# MidiIO.net
KiCad netlist of a schematic drawn in EAGLE
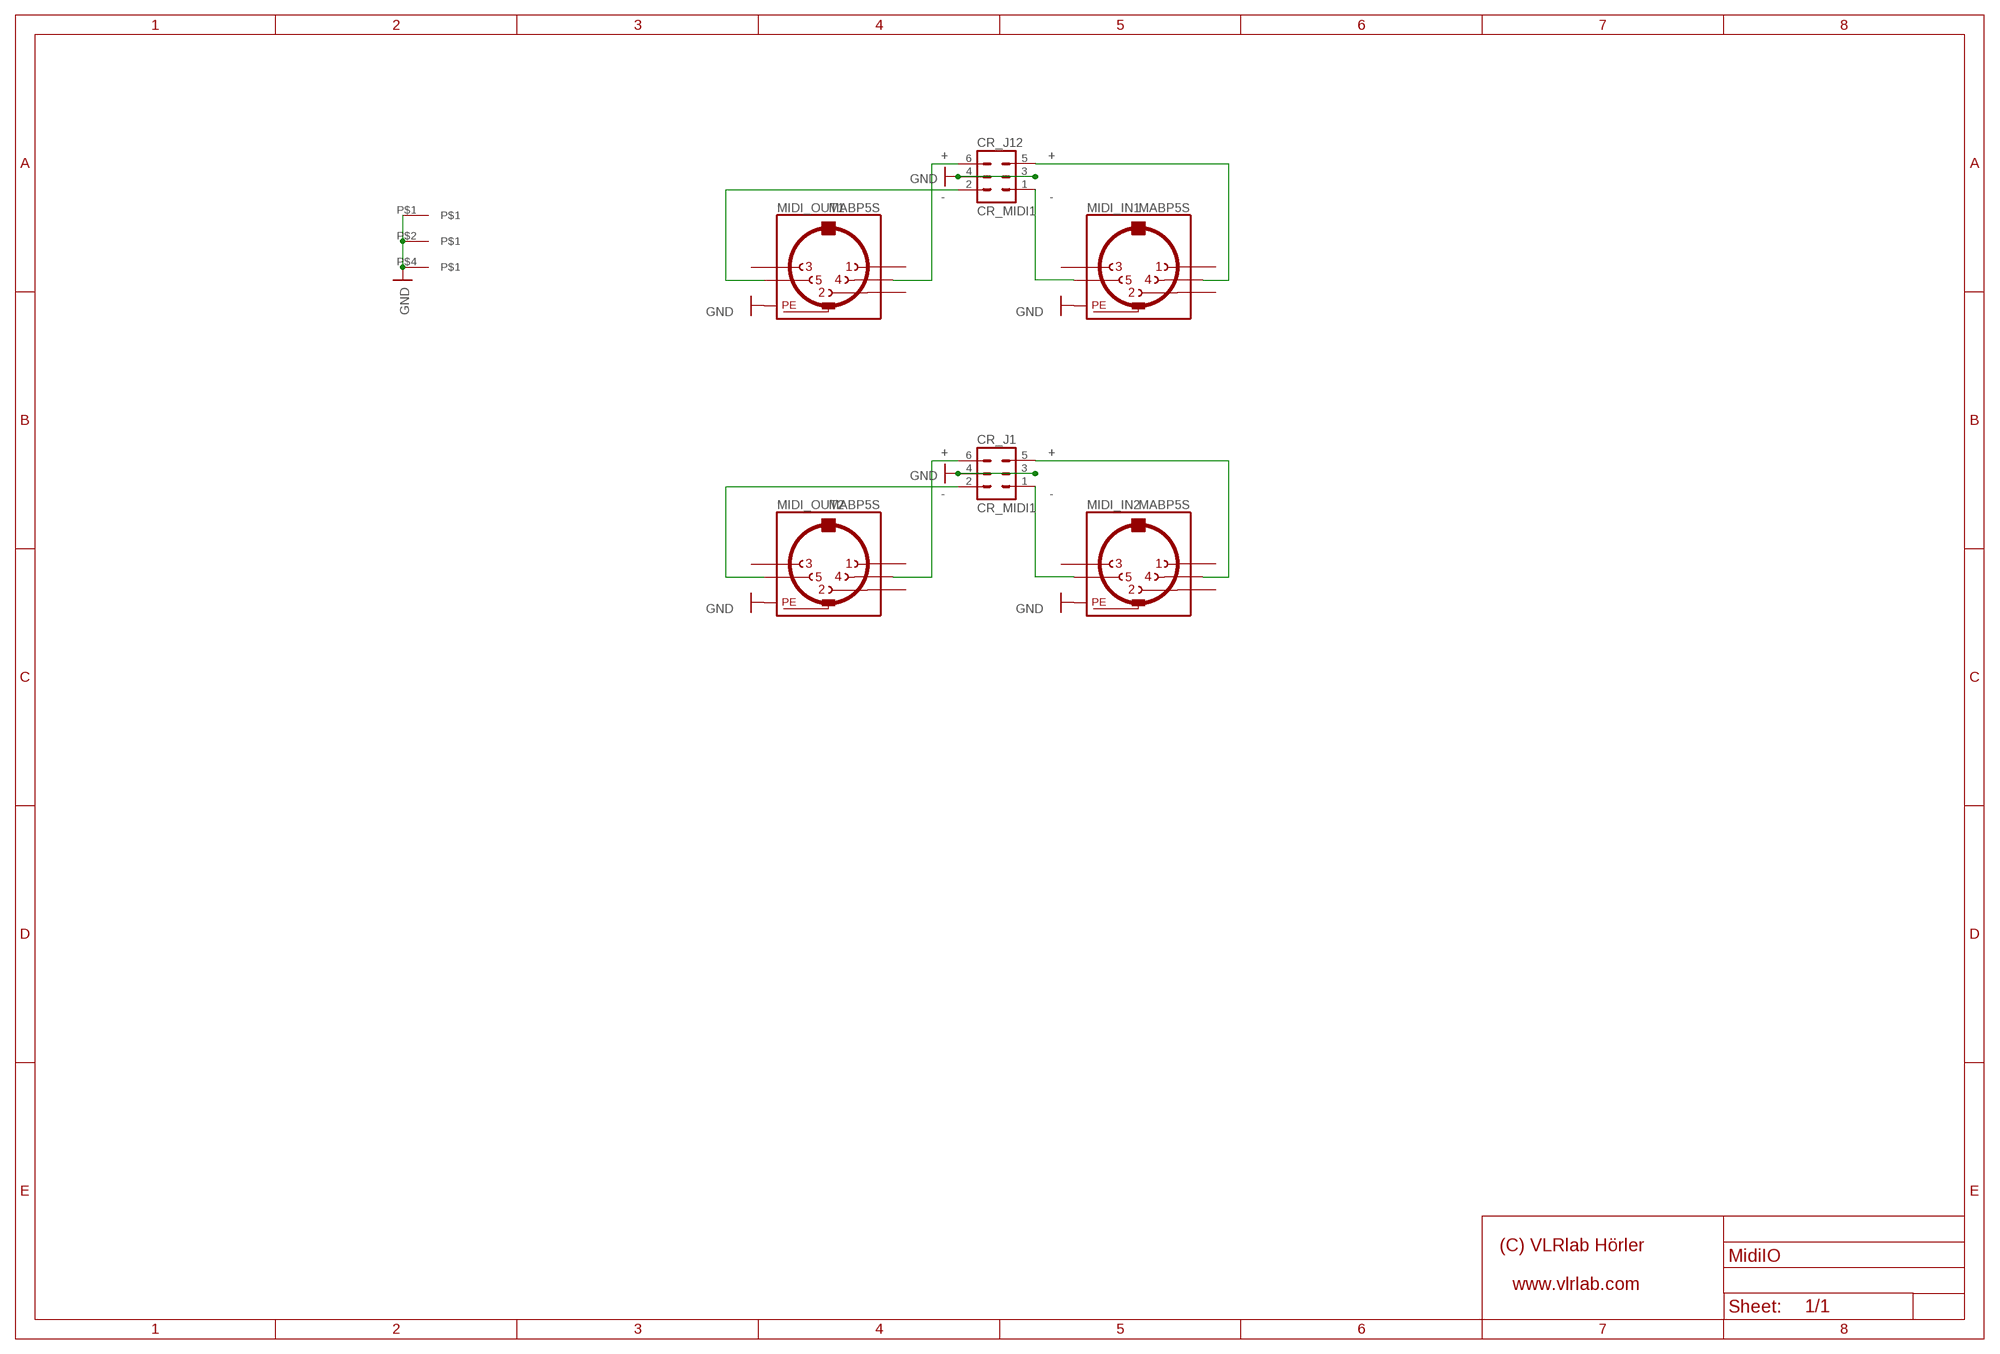
[diagram p0: schematic, sheet 1]

(export (version "E")
  (design (tool "Eeschema 10.0.6"))
  (components
    (comp (ref "CR_J1")
      (value "CR_MIDI1")
      (footprint "eagle-import:ML6")
      (libsource (lib "eagle-import") (part "ML6"))
    )
    (comp (ref "CR_J12")
      (value "CR_MIDI1")
      (footprint "eagle-import:ML6")
      (libsource (lib "eagle-import") (part "ML6"))
    )
    (comp (ref "MIDI_IN1")
      (value "MABP5S")
      (footprint "eagle-import:MABP5S")
      (libsource (lib "eagle-import") (part "MABP5S"))
    )
    (comp (ref "MIDI_IN2")
      (value "MABP5S")
      (footprint "eagle-import:MABP5S")
      (libsource (lib "eagle-import") (part "MABP5S"))
    )
    (comp (ref "MIDI_OUT1")
      (value "MABP5S")
      (footprint "eagle-import:MABP5S")
      (libsource (lib "eagle-import") (part "MABP5S"))
    )
    (comp (ref "MIDI_OUT2")
      (value "MABP5S")
      (footprint "eagle-import:MABP5S")
      (libsource (lib "eagle-import") (part "MABP5S"))
    )
    (comp (ref "U$2")
      (value "MIDIBOX_HALF_FRONTLINE")
      (footprint "eagle-import:MIDIBOX14X6-FRONTLINE")
      (libsource (lib "eagle-import") (part "MIDIBOX_HALF_FRONTLINE"))
    )
  )
  (nets
    (net (code "1") (name "GND") (class "Default")
      (node (ref "CR_J1") (pin "3") (pinfunction "3_3") (pintype "passive"))
      (node (ref "CR_J1") (pin "4") (pinfunction "4_4") (pintype "passive"))
      (node (ref "CR_J12") (pin "3") (pinfunction "3_3") (pintype "passive"))
      (node (ref "CR_J12") (pin "4") (pinfunction "4_4") (pintype "passive"))
      (node (ref "MIDI_IN1") (pin "PE") (pinfunction "PE_PE") (pintype "power_in"))
      (node (ref "MIDI_IN1") (pin "PE@") (pinfunction "PE_PE@") (pintype "power_in"))
      (node (ref "MIDI_IN2") (pin "PE") (pinfunction "PE_PE") (pintype "power_in"))
      (node (ref "MIDI_IN2") (pin "PE@") (pinfunction "PE_PE@") (pintype "power_in"))
      (node (ref "MIDI_OUT1") (pin "PE") (pinfunction "PE_PE") (pintype "power_in"))
      (node (ref "MIDI_OUT1") (pin "PE@") (pinfunction "PE_PE@") (pintype "power_in"))
      (node (ref "MIDI_OUT2") (pin "PE") (pinfunction "PE_PE") (pintype "power_in"))
      (node (ref "MIDI_OUT2") (pin "PE@") (pinfunction "PE_PE@") (pintype "power_in"))
      (node (ref "U$2") (pin "P$1") (pinfunction "P$1_P$1") (pintype "bidirectional"))
      (node (ref "U$2") (pin "P$2") (pinfunction "P$1_P$2") (pintype "bidirectional"))
      (node (ref "U$2") (pin "P$4") (pinfunction "P$1_P$4") (pintype "bidirectional"))
    )
    (net (code "2") (name "Net-(CR_J1-Pad1)") (class "Default")
      (node (ref "CR_J1") (pin "1") (pinfunction "1_1") (pintype "passive"))
      (node (ref "MIDI_IN2") (pin "5") (pinfunction "5_5") (pintype "passive"))
    )
    (net (code "3") (name "Net-(CR_J1-Pad2)") (class "Default")
      (node (ref "CR_J1") (pin "2") (pinfunction "2_2") (pintype "passive"))
      (node (ref "MIDI_OUT2") (pin "5") (pinfunction "5_5") (pintype "passive"))
    )
    (net (code "4") (name "Net-(CR_J1-Pad5)") (class "Default")
      (node (ref "CR_J1") (pin "5") (pinfunction "5_5") (pintype "passive"))
      (node (ref "MIDI_IN2") (pin "4") (pinfunction "4_4") (pintype "passive"))
    )
    (net (code "5") (name "Net-(CR_J1-Pad6)") (class "Default")
      (node (ref "CR_J1") (pin "6") (pinfunction "6_6") (pintype "passive"))
      (node (ref "MIDI_OUT2") (pin "4") (pinfunction "4_4") (pintype "passive"))
    )
    (net (code "6") (name "Net-(CR_J12-Pad1)") (class "Default")
      (node (ref "CR_J12") (pin "1") (pinfunction "1_1") (pintype "passive"))
      (node (ref "MIDI_IN1") (pin "5") (pinfunction "5_5") (pintype "passive"))
    )
    (net (code "7") (name "Net-(CR_J12-Pad2)") (class "Default")
      (node (ref "CR_J12") (pin "2") (pinfunction "2_2") (pintype "passive"))
      (node (ref "MIDI_OUT1") (pin "5") (pinfunction "5_5") (pintype "passive"))
    )
    (net (code "8") (name "Net-(CR_J12-Pad5)") (class "Default")
      (node (ref "CR_J12") (pin "5") (pinfunction "5_5") (pintype "passive"))
      (node (ref "MIDI_IN1") (pin "4") (pinfunction "4_4") (pintype "passive"))
    )
    (net (code "9") (name "Net-(CR_J12-Pad6)") (class "Default")
      (node (ref "CR_J12") (pin "6") (pinfunction "6_6") (pintype "passive"))
      (node (ref "MIDI_OUT1") (pin "4") (pinfunction "4_4") (pintype "passive"))
    )
    (net (code "10") (name "unconnected-(MIDI_IN1-Pad1)") (class "Default")
      (node (ref "MIDI_IN1") (pin "1") (pinfunction "1_1") (pintype "passive"))
    )
    (net (code "11") (name "unconnected-(MIDI_IN1-Pad2)") (class "Default")
      (node (ref "MIDI_IN1") (pin "2") (pinfunction "2_2") (pintype "passive"))
    )
    (net (code "12") (name "unconnected-(MIDI_IN1-Pad3)") (class "Default")
      (node (ref "MIDI_IN1") (pin "3") (pinfunction "3_3") (pintype "passive"))
    )
    (net (code "13") (name "unconnected-(MIDI_IN2-Pad1)") (class "Default")
      (node (ref "MIDI_IN2") (pin "1") (pinfunction "1_1") (pintype "passive"))
    )
    (net (code "14") (name "unconnected-(MIDI_IN2-Pad2)") (class "Default")
      (node (ref "MIDI_IN2") (pin "2") (pinfunction "2_2") (pintype "passive"))
    )
    (net (code "15") (name "unconnected-(MIDI_IN2-Pad3)") (class "Default")
      (node (ref "MIDI_IN2") (pin "3") (pinfunction "3_3") (pintype "passive"))
    )
    (net (code "16") (name "unconnected-(MIDI_OUT1-Pad1)") (class "Default")
      (node (ref "MIDI_OUT1") (pin "1") (pinfunction "1_1") (pintype "passive"))
    )
    (net (code "17") (name "unconnected-(MIDI_OUT1-Pad2)") (class "Default")
      (node (ref "MIDI_OUT1") (pin "2") (pinfunction "2_2") (pintype "passive"))
    )
    (net (code "18") (name "unconnected-(MIDI_OUT1-Pad3)") (class "Default")
      (node (ref "MIDI_OUT1") (pin "3") (pinfunction "3_3") (pintype "passive"))
    )
    (net (code "19") (name "unconnected-(MIDI_OUT2-Pad1)") (class "Default")
      (node (ref "MIDI_OUT2") (pin "1") (pinfunction "1_1") (pintype "passive"))
    )
    (net (code "20") (name "unconnected-(MIDI_OUT2-Pad2)") (class "Default")
      (node (ref "MIDI_OUT2") (pin "2") (pinfunction "2_2") (pintype "passive"))
    )
    (net (code "21") (name "unconnected-(MIDI_OUT2-Pad3)") (class "Default")
      (node (ref "MIDI_OUT2") (pin "3") (pinfunction "3_3") (pintype "passive"))
    )
  )
)
